# isolation.net
KiCad netlist of a schematic drawn in Altium Designer
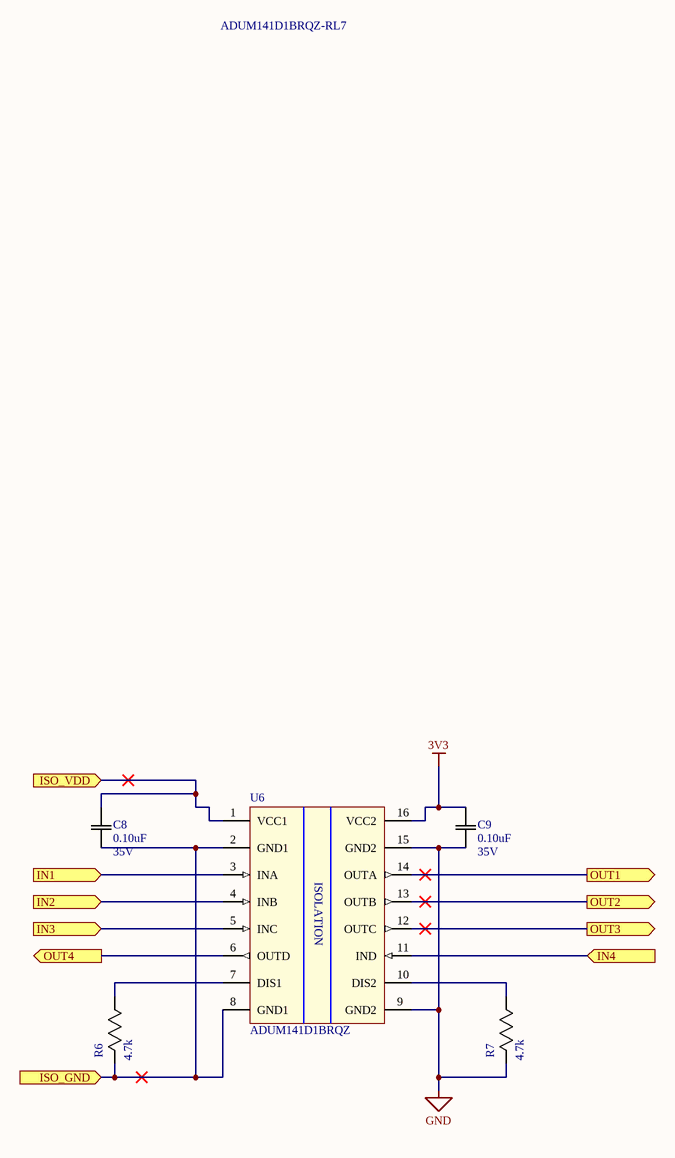
[diagram p0: isolation.SchDoc]

(export (version "E")
  (design (tool "Eeschema 10.0.6"))
  (components
    (comp (ref "C8")
      (value "0.10uF")
      (footprint "0603")
      (description "CAP CER 0.10UF 35V X7R 0603/0805")
      (fields (field (name "TOLERANCE") "10%") (field (name "RATING") "35V"))
      (libsource (lib "AltiumLibraries") (part "CAP 0.10uF 35V"))
    )
    (comp (ref "C9")
      (value "0.10uF")
      (footprint "0603")
      (description "CAP CER 0.10UF 35V X7R 0603/0805")
      (fields (field (name "TOLERANCE") "10%") (field (name "RATING") "35V"))
      (libsource (lib "AltiumLibraries") (part "CAP 0.10uF 35V"))
    )
    (comp (ref "R6")
      (value "4.7k")
      (footprint "0603")
      (description "RES SMD 4.7k OHM 5% 1/8W 0805")
      (fields (field (name "TOLERANCE") "5%"))
      (libsource (lib "AltiumLibraries") (part "RES 4.7k 1/8W - 5%"))
    )
    (comp (ref "R7")
      (value "4.7k")
      (footprint "0603")
      (description "RES SMD 4.7k OHM 5% 1/8W 0805")
      (fields (field (name "TOLERANCE") "5%"))
      (libsource (lib "AltiumLibraries") (part "RES 4.7k 1/8W - 5%"))
    )
    (comp (ref "U6")
      (value "ADUM141D1BRQZ")
      (footprint "SOP64P600X175-16N")
      (description "Digital Isolator CMOS 4-CH 150Mbps 16-Pin QSOP T/R")
      (fields
        (field (name "MANUFACTURER") "Analog Devices")
        (field (name "MANUFACTURER PART NUMBER") "ADUM141D1BRQZ-RL7")
        (field (name "SUPPLIER PART NUMBER 1") "ADUM141D1BRQZ-RL7")
      )
      (libsource (lib "AltiumLibraries") (part "ISO ADUM141D1BRQZ"))
    )
  )
  (nets
    (net (code "1") (name "/IN1") (class "Default")
      (node (ref "U6") (pin "3") (pinfunction "INA_3") (pintype "input"))
    )
    (net (code "2") (name "/IN2") (class "Default")
      (node (ref "U6") (pin "4") (pinfunction "INB_4") (pintype "input"))
    )
    (net (code "3") (name "/IN3") (class "Default")
      (node (ref "U6") (pin "5") (pinfunction "INC_5") (pintype "input"))
    )
    (net (code "4") (name "/IN4") (class "Default")
      (node (ref "U6") (pin "11") (pinfunction "IND_11") (pintype "input"))
    )
    (net (code "5") (name "/ISO_GND") (class "Default")
      (node (ref "C8") (pin "1") (pinfunction "C1_1") (pintype "passive"))
      (node (ref "R6") (pin "2") (pinfunction "R2_2") (pintype "passive"))
      (node (ref "U6") (pin "2") (pinfunction "GND1_2") (pintype "power_in"))
      (node (ref "U6") (pin "8") (pinfunction "GND1_8") (pintype "power_in"))
    )
    (net (code "6") (name "/ISO_VDD") (class "Default")
      (node (ref "C8") (pin "2") (pinfunction "C2_2") (pintype "passive"))
      (node (ref "U6") (pin "1") (pinfunction "VCC1_1") (pintype "power_in"))
    )
    (net (code "7") (name "/OUT1") (class "Default")
      (node (ref "U6") (pin "14") (pinfunction "OUTA_14") (pintype "output"))
    )
    (net (code "8") (name "/OUT2") (class "Default")
      (node (ref "U6") (pin "13") (pinfunction "OUTB_13") (pintype "output"))
    )
    (net (code "9") (name "/OUT3") (class "Default")
      (node (ref "U6") (pin "12") (pinfunction "OUTC_12") (pintype "output"))
    )
    (net (code "10") (name "/OUT4") (class "Default")
      (node (ref "U6") (pin "6") (pinfunction "OUTD_6") (pintype "output"))
    )
    (net (code "11") (name "3V3") (class "Default")
      (node (ref "C9") (pin "2") (pinfunction "C2_2") (pintype "passive"))
      (node (ref "U6") (pin "16") (pinfunction "VCC2_16") (pintype "power_in"))
    )
    (net (code "12") (name "GND") (class "Default")
      (node (ref "C9") (pin "1") (pinfunction "C1_1") (pintype "passive"))
      (node (ref "R7") (pin "2") (pinfunction "R2_2") (pintype "passive"))
      (node (ref "U6") (pin "15") (pinfunction "GND2_15") (pintype "power_in"))
      (node (ref "U6") (pin "9") (pinfunction "GND2_9") (pintype "power_in"))
    )
    (net (code "13") (name "Net-(R6-R1)") (class "Default")
      (node (ref "R6") (pin "1") (pinfunction "R1_1") (pintype "passive"))
      (node (ref "U6") (pin "7") (pinfunction "DIS1_7") (pintype "passive"))
    )
    (net (code "14") (name "Net-(R7-R1)") (class "Default")
      (node (ref "R7") (pin "1") (pinfunction "R1_1") (pintype "passive"))
      (node (ref "U6") (pin "10") (pinfunction "DIS2_10") (pintype "passive"))
    )
  )
)
